# MainBoard_AD9835.net
KiCad netlist of a schematic drawn in Altium Designer
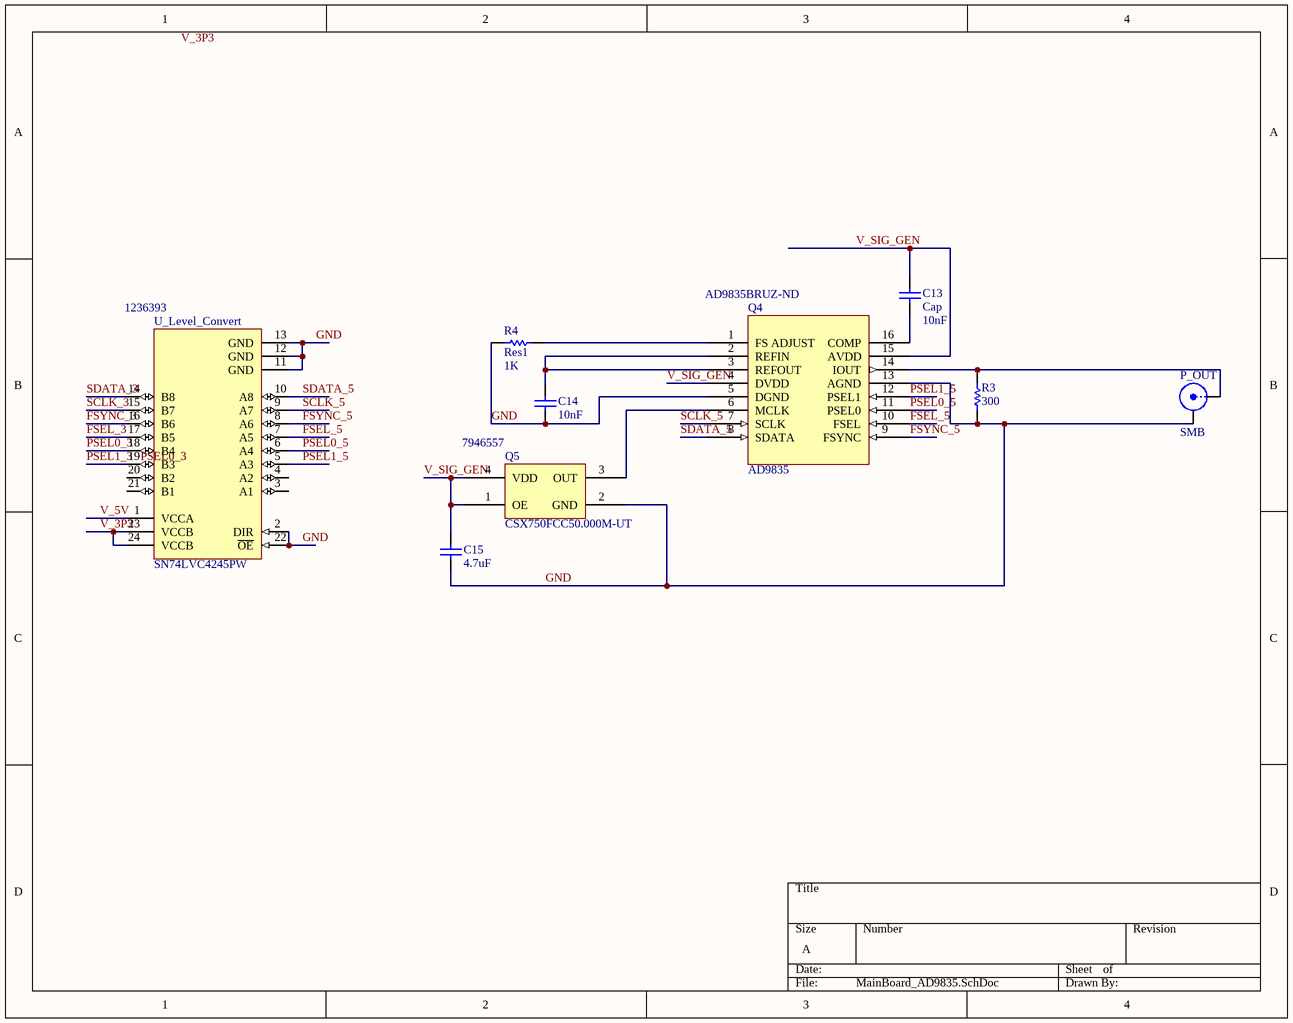
[diagram p0: MainBoard_AD9835.SchDoc]

(export (version "E")
  (design (tool "Eeschema 10.0.6"))
  (components
    (comp (ref "C13")
      (value "Cap")
      (footprint "CAPR2.54-5.1x3.2")
      (description "Capacitor")
      (fields (field (name "ALTIUM_VALUE") "10nF") (field (name "PUBLISHER") "Altium Limited"))
      (libsource (lib "Miscellaneous Devices") (part "Cap"))
    )
    (comp (ref "C14")
      (value "10nF")
      (footprint "CAPR2.54-5.1x3.2")
      (description "Capacitor")
      (fields (field (name "Comment") "Cap") (field (name "PUBLISHER") "Altium Limited"))
      (libsource (lib "Miscellaneous Devices") (part "Cap"))
    )
    (comp (ref "C15")
      (value "4.7uF")
      (footprint "CAPR2.54-5.1x3.2")
      (description "Capacitor")
      (fields (field (name "Comment") "Cap") (field (name "PUBLISHER") "Altium Limited"))
      (libsource (lib "Miscellaneous Devices") (part "Cap"))
    )
    (comp (ref "P_OUT")
      (value "SMB")
      (footprint "SMB_V-RJ45")
      (description "SMB Straight Connector")
      (fields (field (name "PUBLISHER") "Altium Limited"))
      (libsource (lib "Miscellaneous Connectors") (part "SMB"))
    )
    (comp (ref "Q4")
      (value "AD9835")
      (footprint "Maxim Footprints:TSSOP16")
      (fields (field (name "SUPPLIER PART NUMBER 1") "AD9835BRUZ-ND"))
      (libsource (lib "MainBoard_Lib") (part "AD9835"))
    )
    (comp (ref "Q5")
      (value "CSX750FCC50.000M-UT")
      (footprint "CSX750")
      (fields (field (name "SUPPLIER PART NUMBER 1") "7946557"))
      (libsource (lib "MainBoard_Lib") (part "CSX750FCC50.000M-UT"))
    )
    (comp (ref "R3")
      (value "300")
      (footprint "AXIAL-0.3")
      (description "Resistor")
      (fields (field (name "Comment") "Res1") (field (name "PUBLISHER") "Altium Limited"))
      (libsource (lib "Miscellaneous Devices") (part "Res1"))
    )
    (comp (ref "R4")
      (value "Res1")
      (footprint "AXIAL-0.3")
      (description "Resistor")
      (fields (field (name "ALTIUM_VALUE") "1K") (field (name "PUBLISHER") "Altium Limited"))
      (libsource (lib "Miscellaneous Devices") (part "Res1"))
    )
    (comp (ref "U_Level_Convert")
      (value "SN74LVC4245PW")
      (footprint "PW024")
      (description "Octal Bus Transceiver and 3.3-V to 5-V Shifter with 3-State Outputs")
      (fields (field (name "SUPPLIER PART NUMBER 1") "1236393") (field (name "PUBLISHER") "Altium Limited"))
      (libsource (lib "TI Interface 8-Bit Line Transceiver") (part "SN74LVC4245PW"))
    )
  )
  (nets
    (net (code "1") (name "/FSEL_3") (class "Default")
      (node (ref "U_Level_Convert") (pin "17") (pinfunction "B5_17") (pintype "bidirectional"))
    )
    (net (code "2") (name "/FSEL_5") (class "Default")
      (node (ref "Q4") (pin "10") (pinfunction "FSEL_10") (pintype "input"))
      (node (ref "U_Level_Convert") (pin "7") (pinfunction "A5_7") (pintype "bidirectional"))
    )
    (net (code "3") (name "/FSYNC_3") (class "Default")
      (node (ref "U_Level_Convert") (pin "16") (pinfunction "B6_16") (pintype "bidirectional"))
    )
    (net (code "4") (name "/FSYNC_5") (class "Default")
      (node (ref "Q4") (pin "9") (pinfunction "FSYNC_9") (pintype "input"))
      (node (ref "U_Level_Convert") (pin "8") (pinfunction "A6_8") (pintype "bidirectional"))
    )
    (net (code "5") (name "/GND") (class "Default")
      (node (ref "C14") (pin "1") (pinfunction "1_1") (pintype "passive"))
      (node (ref "C15") (pin "1") (pinfunction "1_1") (pintype "passive"))
      (node (ref "P_OUT") (pin "2") (pinfunction "Y_2") (pintype "passive"))
      (node (ref "Q4") (pin "13") (pinfunction "AGND_13") (pintype "power_in"))
      (node (ref "Q4") (pin "5") (pinfunction "DGND_5") (pintype "power_in"))
      (node (ref "Q5") (pin "2") (pinfunction "GND_2") (pintype "passive"))
      (node (ref "R3") (pin "1") (pinfunction "1_1") (pintype "passive"))
      (node (ref "R4") (pin "1") (pinfunction "1_1") (pintype "passive"))
      (node (ref "U_Level_Convert") (pin "11") (pinfunction "GND_11") (pintype "power_in"))
      (node (ref "U_Level_Convert") (pin "12") (pinfunction "GND_12") (pintype "power_in"))
      (node (ref "U_Level_Convert") (pin "13") (pinfunction "GND_13") (pintype "power_in"))
      (node (ref "U_Level_Convert") (pin "2") (pinfunction "DIR_2") (pintype "input"))
      (node (ref "U_Level_Convert") (pin "22") (pinfunction "~{OE}_22") (pintype "input"))
    )
    (net (code "6") (name "/PSEL0_3") (class "Default")
      (node (ref "U_Level_Convert") (pin "18") (pinfunction "B4_18") (pintype "bidirectional"))
    )
    (net (code "7") (name "/PSEL0_5") (class "Default")
      (node (ref "Q4") (pin "11") (pinfunction "PSEL0_11") (pintype "input"))
      (node (ref "U_Level_Convert") (pin "6") (pinfunction "A4_6") (pintype "bidirectional"))
    )
    (net (code "8") (name "/PSEL1_3") (class "Default")
      (node (ref "U_Level_Convert") (pin "19") (pinfunction "B3_19") (pintype "bidirectional"))
    )
    (net (code "9") (name "/PSEL1_5") (class "Default")
      (node (ref "Q4") (pin "12") (pinfunction "PSEL1_12") (pintype "input"))
      (node (ref "U_Level_Convert") (pin "5") (pinfunction "A3_5") (pintype "bidirectional"))
    )
    (net (code "10") (name "/SCLK_3") (class "Default")
      (node (ref "U_Level_Convert") (pin "15") (pinfunction "B7_15") (pintype "bidirectional"))
    )
    (net (code "11") (name "/SCLK_5") (class "Default")
      (node (ref "Q4") (pin "7") (pinfunction "SCLK_7") (pintype "input"))
      (node (ref "U_Level_Convert") (pin "9") (pinfunction "A7_9") (pintype "bidirectional"))
    )
    (net (code "12") (name "/SDATA_3") (class "Default")
      (node (ref "U_Level_Convert") (pin "14") (pinfunction "B8_14") (pintype "bidirectional"))
    )
    (net (code "13") (name "/SDATA_5") (class "Default")
      (node (ref "Q4") (pin "8") (pinfunction "SDATA_8") (pintype "input"))
      (node (ref "U_Level_Convert") (pin "10") (pinfunction "A8_10") (pintype "bidirectional"))
    )
    (net (code "14") (name "/V_3P3") (class "Default")
      (node (ref "U_Level_Convert") (pin "23") (pinfunction "VCCB_23") (pintype "power_in"))
      (node (ref "U_Level_Convert") (pin "24") (pinfunction "VCCB_24") (pintype "power_in"))
    )
    (net (code "15") (name "/V_5V") (class "Default")
      (node (ref "U_Level_Convert") (pin "1") (pinfunction "VCCA_1") (pintype "power_in"))
    )
    (net (code "16") (name "/V_SIG_GEN") (class "Default")
      (node (ref "C13") (pin "2") (pinfunction "2_2") (pintype "passive"))
      (node (ref "C15") (pin "2") (pinfunction "2_2") (pintype "passive"))
      (node (ref "Q4") (pin "15") (pinfunction "AVDD_15") (pintype "power_in"))
      (node (ref "Q4") (pin "4") (pinfunction "DVDD_4") (pintype "power_in"))
      (node (ref "Q5") (pin "1") (pinfunction "OE_1") (pintype "passive"))
      (node (ref "Q5") (pin "4") (pinfunction "VDD_4") (pintype "passive"))
    )
    (net (code "17") (name "Net-(P_OUT-X)") (class "Default")
      (node (ref "P_OUT") (pin "1") (pinfunction "X_1") (pintype "passive"))
      (node (ref "Q4") (pin "14") (pinfunction "IOUT_14") (pintype "output"))
      (node (ref "R3") (pin "2") (pinfunction "2_2") (pintype "passive"))
    )
    (net (code "18") (name "Net-(Q4-COMP)") (class "Default")
      (node (ref "C13") (pin "1") (pinfunction "1_1") (pintype "passive"))
      (node (ref "Q4") (pin "16") (pinfunction "COMP_16") (pintype "passive"))
    )
    (net (code "19") (name "Net-(Q4-FS_ADJUST)") (class "Default")
      (node (ref "Q4") (pin "1") (pinfunction "FS_ADJUST_1") (pintype "passive"))
      (node (ref "R4") (pin "2") (pinfunction "2_2") (pintype "passive"))
    )
    (net (code "20") (name "Net-(Q4-MCLK)") (class "Default")
      (node (ref "Q4") (pin "6") (pinfunction "MCLK_6") (pintype "passive"))
      (node (ref "Q5") (pin "3") (pinfunction "OUT_3") (pintype "passive"))
    )
    (net (code "21") (name "Net-(Q4-REFIN)") (class "Default")
      (node (ref "C14") (pin "2") (pinfunction "2_2") (pintype "passive"))
      (node (ref "Q4") (pin "2") (pinfunction "REFIN_2") (pintype "passive"))
      (node (ref "Q4") (pin "3") (pinfunction "REFOUT_3") (pintype "passive"))
    )
    (net (code "22") (name "unconnected-(U_Level_Convert-A1-Pad3)") (class "Default")
      (node (ref "U_Level_Convert") (pin "3") (pinfunction "A1_3") (pintype "bidirectional"))
    )
    (net (code "23") (name "unconnected-(U_Level_Convert-A2-Pad4)") (class "Default")
      (node (ref "U_Level_Convert") (pin "4") (pinfunction "A2_4") (pintype "bidirectional"))
    )
    (net (code "24") (name "unconnected-(U_Level_Convert-B1-Pad21)") (class "Default")
      (node (ref "U_Level_Convert") (pin "21") (pinfunction "B1_21") (pintype "bidirectional"))
    )
    (net (code "25") (name "unconnected-(U_Level_Convert-B2-Pad20)") (class "Default")
      (node (ref "U_Level_Convert") (pin "20") (pinfunction "B2_20") (pintype "bidirectional"))
    )
  )
)
